# SV601275A.net
KiCad netlist of a schematic drawn in Altium Designer
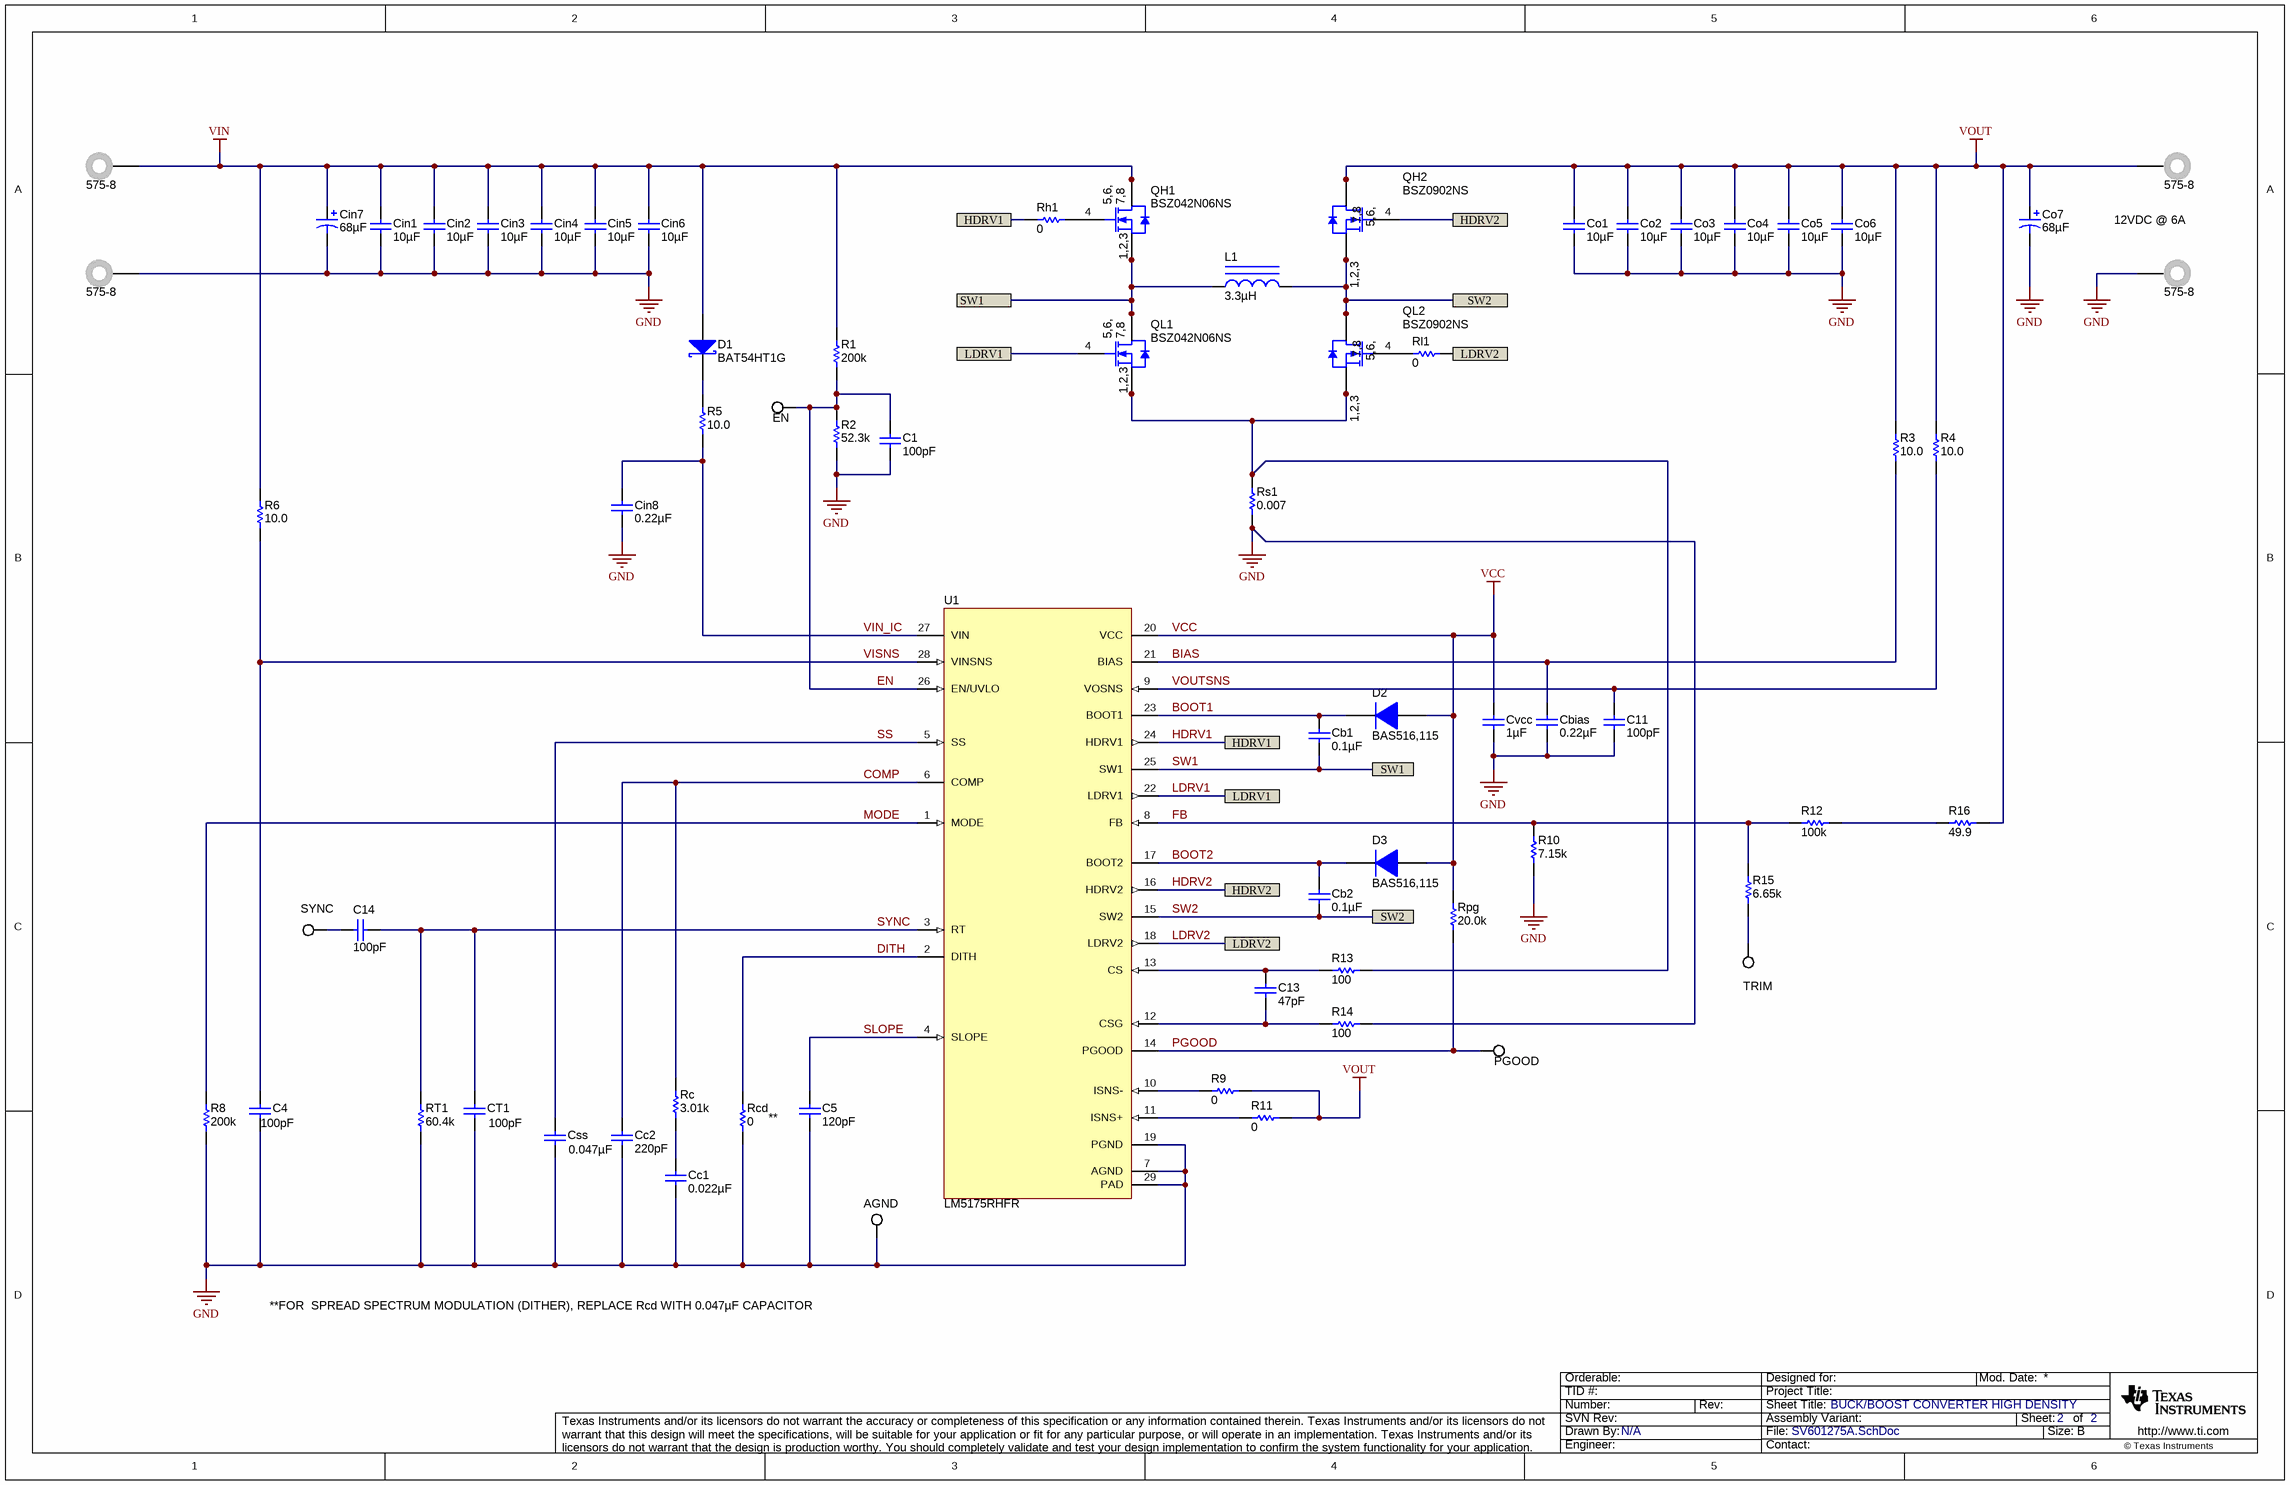
[diagram p0: SV601275A.SchDoc]

(export (version "E")
  (design (tool "Eeschema 10.0.6"))
  (components
    (comp (ref "AGND")
      (value "5015")
      (footprint "Testpoint_Keystone_Miniature")
      (description "Test Point, Miniature, SMT")
      (fields (field (name "MANUFACTURER") "Keystone") (field (name "PUBLISHER") "Texas Instruments"))
      (libsource (lib "Connectors_Keystone") (part "5015"))
    )
    (comp (ref "C1")
      (value "GRM1885C1H101JA01D")
      (footprint "0603L")
      (description "CAP, CERM, 100pF, 50V, +/-5%, C0G/NP0, 0603")
      (fields
        (field (name "VALUEDISPLAYED") "100pF")
        (field (name "MANUFACTURER") "MuRata")
        (field (name "PUBLISHER") "Texas Instruments")
      )
      (libsource (lib "Capacitor_Ceramic") (part "GRM1885C1H101JA01D"))
    )
    (comp (ref "C4")
      (value "GRM1885C1H101JA01D")
      (footprint "0603L")
      (description "CAP, CERM, 100pF, 50V, +/-5%, C0G/NP0, 0603")
      (fields
        (field (name "VALUEDISPLAYED") "100pF")
        (field (name "MANUFACTURER") "MuRata")
        (field (name "PUBLISHER") "Texas Instruments")
      )
      (libsource (lib "Capacitor_Ceramic") (part "GRM1885C1H101JA01D"))
    )
    (comp (ref "C5")
      (value "GRM1885C1H121JA01D")
      (footprint "0603L")
      (description "CAP, CERM, 120pF, 50V, +/-5%, C0G/NP0, 0603")
      (fields
        (field (name "VALUEDISPLAYED") "120pF")
        (field (name "MANUFACTURER") "MuRata")
        (field (name "PUBLISHER") "Texas Instruments")
      )
      (libsource (lib "Capacitor_Ceramic") (part "GRM1885C1H121JA01D"))
    )
    (comp (ref "C11")
      (value "GRM1885C1H101JA01D")
      (footprint "0603L")
      (description "CAP, CERM, 100pF, 50V, +/-5%, C0G/NP0, 0603")
      (fields
        (field (name "VALUEDISPLAYED") "100pF")
        (field (name "MANUFACTURER") "MuRata")
        (field (name "PUBLISHER") "Texas Instruments")
      )
      (libsource (lib "Capacitor_Ceramic") (part "GRM1885C1H101JA01D"))
    )
    (comp (ref "C13")
      (value "GRM1885C1H470JA01D")
      (footprint "0603L")
      (description "CAP, CERM, 47pF, 50V, +/-5%, C0G/NP0, 0603")
      (fields
        (field (name "VALUEDISPLAYED") "47pF")
        (field (name "MANUFACTURER") "MuRata")
        (field (name "PUBLISHER") "Texas Instruments")
      )
      (libsource (lib "Capacitor_Ceramic") (part "GRM1885C1H470JA01D"))
    )
    (comp (ref "C14")
      (value "CGA3E2NP01H101J080AA")
      (footprint "0603L")
      (description "CAP, CERM, 100pF, 50V, +/-5%, C0G/NP0, 0603")
      (fields
        (field (name "VALUEDISPLAYED") "100pF")
        (field (name "MANUFACTURER") "TDK")
        (field (name "PUBLISHER") "Texas Instruments")
      )
      (libsource (lib "Capacitor_Ceramic") (part "CGA3E2NP01H101J080AA"))
    )
    (comp (ref "Cb1")
      (value "GCM188R71H104KA57D")
      (footprint "0603L")
      (description "CAP, CERM, 0.1uF, 50V, +/-10%, X7R, 0603")
      (fields
        (field (name "VALUEDISPLAYED") "0.1µF")
        (field (name "MANUFACTURER") "MuRata")
        (field (name "PUBLISHER") "Texas Instruments")
      )
      (libsource (lib "Capacitor_Ceramic") (part "GCM188R71H104KA57D"))
    )
    (comp (ref "Cb2")
      (value "GCM188R71H104KA57D")
      (footprint "0603L")
      (description "CAP, CERM, 0.1uF, 50V, +/-10%, X7R, 0603")
      (fields
        (field (name "VALUEDISPLAYED") "0.1µF")
        (field (name "MANUFACTURER") "MuRata")
        (field (name "PUBLISHER") "Texas Instruments")
      )
      (libsource (lib "Capacitor_Ceramic") (part "GCM188R71H104KA57D"))
    )
    (comp (ref "Cbias")
      (value "C1608X7R1H224K080AB")
      (footprint "0603_HV")
      (description "CAP, CERM, 0.22uF, 50V, +/-10%, X7R, 0603")
      (fields
        (field (name "VALUEDISPLAYED") "0.22µF")
        (field (name "MANUFACTURER") "TDK")
        (field (name "PUBLISHER") "Texas Instruments")
      )
      (libsource (lib "Capacitor_Ceramic") (part "C1608X7R1H224K080AB"))
    )
    (comp (ref "Cc1")
      (value "GRM188R71H223KA01D")
      (footprint "0603L")
      (description "CAP, CERM, 0.022 µF, 50 V, +/- 10%, X7R, 0603")
      (fields
        (field (name "VALUEDISPLAYED") "0.022µF")
        (field (name "MANUFACTURER") "MuRata")
        (field (name "PUBLISHER") "Texas Instruments")
      )
      (libsource (lib "Capacitor_Ceramic") (part "GRM188R71H223KA01D"))
    )
    (comp (ref "Cc2")
      (value "GRM1885C1H221JA01D")
      (footprint "0603L")
      (description "CAP, CERM, 220 pF, 50 V, +/- 5%, C0G/NP0, 0603")
      (fields
        (field (name "VALUEDISPLAYED") "220pF")
        (field (name "MANUFACTURER") "MuRata")
        (field (name "PUBLISHER") "Texas Instruments")
      )
      (libsource (lib "Capacitor_Ceramic") (part "GRM1885C1H221JA01D"))
    )
    (comp (ref "Cin1")
      (value "GRM32ER71H106KA12L")
      (footprint "1210L")
      (description "CAP, CERM, 10uF, 50V, +/-10%, X7R, 1210")
      (fields
        (field (name "VALUEDISPLAYED") "10µF")
        (field (name "MANUFACTURER") "MuRata")
        (field (name "PUBLISHER") "Texas Instruments")
      )
      (libsource (lib "Capacitor_Ceramic") (part "GRM32ER71H106KA12L"))
    )
    (comp (ref "Cin2")
      (value "GRM32ER71H106KA12L")
      (footprint "1210L")
      (description "CAP, CERM, 10uF, 50V, +/-10%, X7R, 1210")
      (fields
        (field (name "VALUEDISPLAYED") "10µF")
        (field (name "MANUFACTURER") "MuRata")
        (field (name "PUBLISHER") "Texas Instruments")
      )
      (libsource (lib "Capacitor_Ceramic") (part "GRM32ER71H106KA12L"))
    )
    (comp (ref "Cin3")
      (value "GRM32ER71H106KA12L")
      (footprint "1210L")
      (description "CAP, CERM, 10uF, 50V, +/-10%, X7R, 1210")
      (fields
        (field (name "VALUEDISPLAYED") "10µF")
        (field (name "MANUFACTURER") "MuRata")
        (field (name "PUBLISHER") "Texas Instruments")
      )
      (libsource (lib "Capacitor_Ceramic") (part "GRM32ER71H106KA12L"))
    )
    (comp (ref "Cin4")
      (value "GRM32ER71H106KA12L")
      (footprint "1210L")
      (description "CAP, CERM, 10uF, 50V, +/-10%, X7R, 1210")
      (fields
        (field (name "VALUEDISPLAYED") "10µF")
        (field (name "MANUFACTURER") "MuRata")
        (field (name "PUBLISHER") "Texas Instruments")
      )
      (libsource (lib "Capacitor_Ceramic") (part "GRM32ER71H106KA12L"))
    )
    (comp (ref "Cin5")
      (value "GRM32ER71H106KA12L")
      (footprint "1210L")
      (description "CAP, CERM, 10uF, 50V, +/-10%, X7R, 1210")
      (fields
        (field (name "VALUEDISPLAYED") "10µF")
        (field (name "MANUFACTURER") "MuRata")
        (field (name "PUBLISHER") "Texas Instruments")
      )
      (libsource (lib "Capacitor_Ceramic") (part "GRM32ER71H106KA12L"))
    )
    (comp (ref "Cin6")
      (value "GRM32ER71H106KA12L")
      (footprint "1210L")
      (description "CAP, CERM, 10uF, 50V, +/-10%, X7R, 1210")
      (fields
        (field (name "VALUEDISPLAYED") "10µF")
        (field (name "MANUFACTURER") "MuRata")
        (field (name "PUBLISHER") "Texas Instruments")
      )
      (libsource (lib "Capacitor_Ceramic") (part "GRM32ER71H106KA12L"))
    )
    (comp (ref "Cin7")
      (value "EEHZC1H680P")
      (footprint "SM_RADIAL_8MM")
      (description "CAP, AL, 68 µF, 50 V, +/- 20%, 30 ohm, SMD")
      (fields
        (field (name "VALUEDISPLAYED") "68µF")
        (field (name "MANUFACTURER") "Panasonic")
        (field (name "PUBLISHER") "Texas Instruments")
      )
      (libsource (lib "Capacitor_Other") (part "EEHZC1H680P"))
    )
    (comp (ref "Cin8")
      (value "C1608X7R1H224K080AB")
      (footprint "0603L")
      (description "CAP, CERM, 0.22uF, 50V, +/-10%, X7R, 0603")
      (fields
        (field (name "VALUEDISPLAYED") "0.22µF")
        (field (name "MANUFACTURER") "TDK")
        (field (name "PUBLISHER") "Texas Instruments")
      )
      (libsource (lib "Capacitor_Ceramic") (part "C1608X7R1H224K080AB"))
    )
    (comp (ref "Co1")
      (value "GRM32ER71H106KA12L")
      (footprint "1210L")
      (description "CAP, CERM, 10 µF, 50 V, +/- 10%, X7R, 1210")
      (fields
        (field (name "VALUEDISPLAYED") "10µF")
        (field (name "MANUFACTURER") "MuRata")
        (field (name "PUBLISHER") "Texas Instruments")
      )
      (libsource (lib "Capacitor_Ceramic") (part "GRM32ER71H106KA12L"))
    )
    (comp (ref "Co2")
      (value "GRM32ER71H106KA12L")
      (footprint "1210L")
      (description "CAP, CERM, 10 µF, 50 V, +/- 10%, X7R, 1210")
      (fields
        (field (name "VALUEDISPLAYED") "10µF")
        (field (name "MANUFACTURER") "MuRata")
        (field (name "PUBLISHER") "Texas Instruments")
      )
      (libsource (lib "Capacitor_Ceramic") (part "GRM32ER71H106KA12L"))
    )
    (comp (ref "Co3")
      (value "GRM32ER71H106KA12L")
      (footprint "1210L")
      (description "CAP, CERM, 10 µF, 50 V, +/- 10%, X7R, 1210")
      (fields
        (field (name "VALUEDISPLAYED") "10µF")
        (field (name "MANUFACTURER") "MuRata")
        (field (name "PUBLISHER") "Texas Instruments")
      )
      (libsource (lib "Capacitor_Ceramic") (part "GRM32ER71H106KA12L"))
    )
    (comp (ref "Co4")
      (value "GRM32ER71H106KA12L")
      (footprint "1210L")
      (description "CAP, CERM, 10 µF, 50 V, +/- 10%, X7R, 1210")
      (fields
        (field (name "VALUEDISPLAYED") "10µF")
        (field (name "MANUFACTURER") "MuRata")
        (field (name "PUBLISHER") "Texas Instruments")
      )
      (libsource (lib "Capacitor_Ceramic") (part "GRM32ER71H106KA12L"))
    )
    (comp (ref "Co5")
      (value "GRM32ER71H106KA12L")
      (footprint "1210L")
      (description "CAP, CERM, 10 µF, 50 V, +/- 10%, X7R, 1210")
      (fields
        (field (name "VALUEDISPLAYED") "10µF")
        (field (name "MANUFACTURER") "MuRata")
        (field (name "PUBLISHER") "Texas Instruments")
      )
      (libsource (lib "Capacitor_Ceramic") (part "GRM32ER71H106KA12L"))
    )
    (comp (ref "Co6")
      (value "GRM32ER71H106KA12L")
      (footprint "1210L")
      (description "CAP, CERM, 10 µF, 50 V, +/- 10%, X7R, 1210")
      (fields
        (field (name "VALUEDISPLAYED") "10µF")
        (field (name "MANUFACTURER") "MuRata")
        (field (name "PUBLISHER") "Texas Instruments")
      )
      (libsource (lib "Capacitor_Ceramic") (part "GRM32ER71H106KA12L"))
    )
    (comp (ref "Co7")
      (value "EEHZC1H680P")
      (footprint "SM_RADIAL_8MM")
      (description "CAP, AL, 68 µF, 50 V, +/- 20%, 30 ohm, SMD")
      (fields
        (field (name "VALUEDISPLAYED") "68µF")
        (field (name "MANUFACTURER") "Panasonic")
        (field (name "PUBLISHER") "Texas Instruments")
      )
      (libsource (lib "Capacitor_Other") (part "EEHZC1H680P"))
    )
    (comp (ref "Css")
      (value "GRM188R71H473KA61D")
      (footprint "0603L")
      (description "CAP, CERM, 0.047 µF, 50 V, +/- 10%, X7R, 0603")
      (fields
        (field (name "VALUEDISPLAYED") "0.047µF")
        (field (name "MANUFACTURER") "MuRata")
        (field (name "PUBLISHER") "Texas Instruments")
      )
      (libsource (lib "Capacitor_Ceramic") (part "GRM188R71H473KA61D"))
    )
    (comp (ref "CT1")
      (value "DNP")
      (footprint "0603L")
      (description "CAP, CERM, 100pF, 50V, +/-5%, C0G/NP0, 0603")
      (fields
        (field (name "PARTNUMBER") "GRM1885C1H101JA01D")
        (field (name "VALUEDISPLAYED") "100pF")
        (field (name "MANUFACTURER") "MuRata")
        (field (name "PUBLISHER") "Texas Instruments")
      )
      (libsource (lib "Capacitor_Ceramic") (part "GRM1885C1H101JA01D"))
    )
    (comp (ref "Cvcc")
      (value "GRM188R71C105KA12D")
      (footprint "0603L")
      (description "CAP, CERM, 1uF, 16V, +/-10%, X7R, 0603")
      (fields
        (field (name "VALUEDISPLAYED") "1µF")
        (field (name "MANUFACTURER") "MuRata")
        (field (name "PUBLISHER") "Texas Instruments")
      )
      (libsource (lib "Capacitor_Ceramic") (part "GRM188R71C105KA12D"))
    )
    (comp (ref "D1")
      (value "BAT54HT1G")
      (footprint "sod-323")
      (description "Diode, Schottky, 30V, 0.2A, SOD-323")
      (fields (field (name "MANUFACTURER") "ON Semiconductor") (field (name "PUBLISHER") "Texas Instruments"))
      (libsource (lib "Diode") (part "BAT54HT1G"))
    )
    (comp (ref "D2")
      (value "BAS516,115")
      (footprint "SOD-523")
      (description "Diode, Switching, 100V, 0.25A, SOD-523")
      (fields
        (field (name "MANUFACTURER") "NXP Semiconductor")
        (field (name "PUBLISHER") "Texas Instruments")
      )
      (libsource (lib "Diode") (part "BAS516,115"))
    )
    (comp (ref "D3")
      (value "BAS516,115")
      (footprint "SOD-523")
      (description "Diode, Switching, 100V, 0.25A, SOD-523")
      (fields
        (field (name "MANUFACTURER") "NXP Semiconductor")
        (field (name "PUBLISHER") "Texas Instruments")
      )
      (libsource (lib "Diode") (part "BAS516,115"))
    )
    (comp (ref "EN")
      (value "5015")
      (footprint "Testpoint_Keystone_Miniature")
      (description "Test Point, Miniature, SMT")
      (fields (field (name "MANUFACTURER") "Keystone") (field (name "PUBLISHER") "Texas Instruments"))
      (libsource (lib "Connectors_Keystone") (part "5015"))
    )
    (comp (ref "J1")
      (value "575-8")
      (footprint "Keystone575-8")
      (description "Standard Banana Jack, Uninsulated, 8.9mm")
      (fields (field (name "MANUFACTURER") "Keystone") (field (name "PUBLISHER") "Texas Instruments"))
      (libsource (lib "Connectors_Keystone") (part "575-8"))
    )
    (comp (ref "J2")
      (value "575-8")
      (footprint "Keystone575-8")
      (description "Standard Banana Jack, Uninsulated, 8.9mm")
      (fields (field (name "MANUFACTURER") "Keystone") (field (name "PUBLISHER") "Texas Instruments"))
      (libsource (lib "Connectors_Keystone") (part "575-8"))
    )
    (comp (ref "J3")
      (value "575-8")
      (footprint "Keystone575-8")
      (description "Standard Banana Jack, Uninsulated, 8.9mm")
      (fields (field (name "MANUFACTURER") "Keystone") (field (name "PUBLISHER") "Texas Instruments"))
      (libsource (lib "Connectors_Keystone") (part "575-8"))
    )
    (comp (ref "J4")
      (value "575-8")
      (footprint "Keystone575-8")
      (description "Standard Banana Jack, Uninsulated, 8.9mm")
      (fields (field (name "MANUFACTURER") "Keystone") (field (name "PUBLISHER") "Texas Instruments"))
      (libsource (lib "Connectors_Keystone") (part "575-8"))
    )
    (comp (ref "L1")
      (value "IHLP5050FDER3R3M01")
      (footprint "IHLP-5050FD")
      (description "Inductor, Shielded Drum Core, Powdered Iron, 3.3 µH, 18 A, 0.0057 ohm, SMD")
      (fields
        (field (name "VALUEDISPLAYED") "3.3µH")
        (field (name "MANUFACTURER") "Vishay-Dale")
        (field (name "PUBLISHER") "Texas Instruments")
      )
      (libsource (lib "Inductor_Vishay") (part "IHLP5050FDER3R3M01"))
    )
    (comp (ref "PGOOD")
      (value "5015")
      (footprint "Testpoint_Keystone_Miniature")
      (description "Test Point, Miniature, SMT")
      (fields (field (name "MANUFACTURER") "Keystone") (field (name "PUBLISHER") "Texas Instruments"))
      (libsource (lib "Connectors_Keystone") (part "5015"))
    )
    (comp (ref "QH1")
      (value "BSZ042N06NS")
      (footprint "FETS:PG-TSDSON-8")
      (description "MOSFET N-CH 60V 19A 8TSDSON")
      (fields (field (name "MANUFACTURER") "Infineon Technologies") (field (name "SYMBOLCREATOR") "Use a-id"))
      (libsource (lib "FETs") (part "BSZ042N06NS"))
    )
    (comp (ref "QH2")
      (value "BSZ0902NS")
      (footprint "PG-TSDSON-8")
      (description "MOSFET, N-CH, 30V, 40A, PG-TSDSON-8")
      (fields
        (field (name "MANUFACTURER") "Infineon Technologies")
        (field (name "PUBLISHER") "Texas Instruments")
      )
      (libsource (lib "FETs") (part "BSZ0902NS"))
    )
    (comp (ref "QL1")
      (value "BSZ042N06NS")
      (footprint "FETS:PG-TSDSON-8")
      (description "MOSFET N-CH 60V 19A 8TSDSON")
      (fields (field (name "MANUFACTURER") "Infineon Technologies") (field (name "SYMBOLCREATOR") "Use a-id"))
      (libsource (lib "FETs") (part "BSZ042N06NS"))
    )
    (comp (ref "QL2")
      (value "BSZ0902NS")
      (footprint "PG-TSDSON-8")
      (description "MOSFET, N-CH, 30V, 40A, PG-TSDSON-8")
      (fields
        (field (name "MANUFACTURER") "Infineon Technologies")
        (field (name "PUBLISHER") "Texas Instruments")
      )
      (libsource (lib "FETs") (part "BSZ0902NS"))
    )
    (comp (ref "R1")
      (value "200k")
      (footprint "0603L")
      (description "RES, 200k ohm, 1%, 0.1W, 0603")
      (fields
        (field (name "PARTNUMBER") "RC0603FR-07200KL")
        (field (name "MANUFACTURER") "Yageo America")
        (field (name "PUBLISHER") "Texas Instruments")
      )
      (libsource (lib "Resistor_0603") (part "RC0603FR-07200KL"))
    )
    (comp (ref "R2")
      (value "RC0603FR-0752K3L")
      (footprint "0603L")
      (description "RES, 52.3 k, 1%, 0.1 W, 0603")
      (fields
        (field (name "MANUFACTURER") "Yageo America")
        (field (name "VALUEDISPLAYED") "52.3k")
        (field (name "PUBLISHER") "Texas Instruments")
      )
      (libsource (lib "Resistor_0603") (part "RC0603FR-0752K3L"))
    )
    (comp (ref "R3")
      (value "10.0")
      (footprint "0603_HV")
      (description "RES, 10.0 ohm, 1%, 0.1W, 0603")
      (fields
        (field (name "PARTNUMBER") "RC0603FR-0710RL")
        (field (name "MANUFACTURER") "Yageo America")
        (field (name "PUBLISHER") "Texas Instruments")
      )
      (libsource (lib "Resistor_0603") (part "RC0603FR-0710RL"))
    )
    (comp (ref "R4")
      (value "CRCW060310R0FKEA")
      (footprint "0603L")
      (description "RES, 10.0, 1%, 0.1 W, 0603")
      (fields
        (field (name "MANUFACTURER") "Vishay-Dale")
        (field (name "VALUEDISPLAYED") "10.0")
        (field (name "PUBLISHER") "Texas Instruments")
      )
      (libsource (lib "Resistor_0603") (part "CRCW060310R0FKEA"))
    )
    (comp (ref "R5")
      (value "10.0")
      (footprint "0603L")
      (description "RES, 10.0 ohm, 1%, 0.1W, 0603")
      (fields
        (field (name "PARTNUMBER") "RC0603FR-0710RL")
        (field (name "MANUFACTURER") "Yageo America")
        (field (name "PUBLISHER") "Texas Instruments")
      )
      (libsource (lib "Resistor_0603") (part "RC0603FR-0710RL"))
    )
    (comp (ref "R6")
      (value "10.0")
      (footprint "0603L")
      (description "RES, 10.0 ohm, 1%, 0.1W, 0603")
      (fields
        (field (name "PARTNUMBER") "RC0603FR-0710RL")
        (field (name "MANUFACTURER") "Yageo America")
        (field (name "PUBLISHER") "Texas Instruments")
      )
      (libsource (lib "Resistor_0603") (part "RC0603FR-0710RL"))
    )
    (comp (ref "R8")
      (value "CRCW0603200KFKEA")
      (footprint "0603L")
      (description "RES, 200 k, 1%, 0.1 W, 0603")
      (fields
        (field (name "MANUFACTURER") "Vishay-Dale")
        (field (name "VALUEDISPLAYED") "200k")
        (field (name "PUBLISHER") "Texas Instruments")
      )
      (libsource (lib "Resistor_0603") (part "CRCW0603200KFKEA"))
    )
    (comp (ref "R9")
      (value "RC0603JR-070RL")
      (footprint "0603L")
      (description "RES, 0, 5%, 0.1 W, 0603")
      (fields
        (field (name "MANUFACTURER") "Yageo America")
        (field (name "VALUEDISPLAYED") "0")
        (field (name "PUBLISHER") "Texas Instruments")
      )
      (libsource (lib "Resistor_0603") (part "RC0603JR-070RL"))
    )
    (comp (ref "R10")
      (value "7.15k")
      (footprint "0603L")
      (description "RES, 7.15k ohm, 1%, 0.1W, 0603")
      (fields
        (field (name "PARTNUMBER") "RC0603FR-077K15L")
        (field (name "MANUFACTURER") "Yageo America")
        (field (name "PUBLISHER") "Texas Instruments")
      )
      (libsource (lib "Resistor_0603") (part "RC0603FR-077K15L"))
    )
    (comp (ref "R11")
      (value "RC0603JR-070RL")
      (footprint "0603L")
      (description "RES, 0, 5%, 0.1 W, 0603")
      (fields
        (field (name "MANUFACTURER") "Yageo America")
        (field (name "VALUEDISPLAYED") "0")
        (field (name "PUBLISHER") "Texas Instruments")
      )
      (libsource (lib "Resistor_0603") (part "RC0603JR-070RL"))
    )
    (comp (ref "R12")
      (value "100k")
      (footprint "0603L")
      (description "RES, 100k ohm, 1%, 0.1W, 0603")
      (fields
        (field (name "PARTNUMBER") "RC0603FR-07100KL")
        (field (name "MANUFACTURER") "Yageo America")
        (field (name "PUBLISHER") "Texas Instruments")
      )
      (libsource (lib "Resistor_0603") (part "RC0603FR-07100KL"))
    )
    (comp (ref "R13")
      (value "100")
      (footprint "0603L")
      (description "RES, 100 ohm, 1%, 0.1W, 0603")
      (fields
        (field (name "PARTNUMBER") "RC0603FR-07100RL")
        (field (name "MANUFACTURER") "Yageo America")
        (field (name "PUBLISHER") "Texas Instruments")
      )
      (libsource (lib "Resistor_0603") (part "RC0603FR-07100RL"))
    )
    (comp (ref "R14")
      (value "100")
      (footprint "0603L")
      (description "RES, 100 ohm, 1%, 0.1W, 0603")
      (fields
        (field (name "PARTNUMBER") "RC0603FR-07100RL")
        (field (name "MANUFACTURER") "Yageo America")
        (field (name "PUBLISHER") "Texas Instruments")
      )
      (libsource (lib "Resistor_0603") (part "RC0603FR-07100RL"))
    )
    (comp (ref "R15")
      (value "RC0603FR-076K65L")
      (footprint "0603L")
      (description "RES, 6.65 k, 1%, 0.1 W, 0603")
      (fields
        (field (name "MANUFACTURER") "Yageo America")
        (field (name "VALUEDISPLAYED") "6.65k")
        (field (name "PUBLISHER") "Texas Instruments")
      )
      (libsource (lib "Resistor_0603") (part "RC0603FR-076K65L"))
    )
    (comp (ref "R16")
      (value "CRCW060349R9FKEA")
      (footprint "0603")
      (description "RES, 49.9, 1%, 0.1 W, 0603")
      (fields
        (field (name "MANUFACTURER") "Vishay-Dale")
        (field (name "VALUEDISPLAYED") "49.9")
        (field (name "PUBLISHER") "Texas Instruments")
      )
      (libsource (lib "Resistor_0603") (part "CRCW060349R9FKEA"))
    )
    (comp (ref "Rc")
      (value "3.01k")
      (footprint "0603L")
      (description "RES, 3.01k ohm, 1%, 0.1W, 0603")
      (fields
        (field (name "PARTNUMBER") "RC0603FR-073K01L")
        (field (name "MANUFACTURER") "Yageo America")
        (field (name "PUBLISHER") "Texas Instruments")
      )
      (libsource (lib "Resistor_0603") (part "RC0603FR-073K01L"))
    )
    (comp (ref "Rcd")
      (value "RC0603JR-070RL")
      (footprint "0603L")
      (description "RES, 0, 5%, 0.1 W, 0603")
      (fields
        (field (name "MANUFACTURER") "Yageo America")
        (field (name "VALUEDISPLAYED") "0")
        (field (name "PUBLISHER") "Texas Instruments")
      )
      (libsource (lib "Resistor_0603") (part "RC0603JR-070RL"))
    )
    (comp (ref "Rh1")
      (value "0")
      (footprint "0603L")
      (description "RES, 0 ohm, 5%, 0.1W, 0603")
      (fields
        (field (name "PARTNUMBER") "CRCW06030000Z0EA")
        (field (name "MANUFACTURER") "Vishay-Dale")
        (field (name "PUBLISHER") "Texas Instruments")
      )
      (libsource (lib "Resistor_0603") (part "CRCW06030000Z0EA"))
    )
    (comp (ref "Rl1")
      (value "0")
      (footprint "0603L")
      (description "RES, 0 ohm, 5%, 0.1W, 0603")
      (fields
        (field (name "PARTNUMBER") "CRCW06030000Z0EA")
        (field (name "MANUFACTURER") "Vishay-Dale")
        (field (name "PUBLISHER") "Texas Instruments")
      )
      (libsource (lib "Resistor_0603") (part "CRCW06030000Z0EA"))
    )
    (comp (ref "Rpg")
      (value "RC0603FR-0720KL")
      (footprint "0603L")
      (description "RES, 20.0 k, 1%, 0.1 W, 0603")
      (fields
        (field (name "MANUFACTURER") "Yageo America")
        (field (name "VALUEDISPLAYED") "20.0k")
        (field (name "PUBLISHER") "Texas Instruments")
      )
      (libsource (lib "Resistor_0603") (part "RC0603FR-0720KL"))
    )
    (comp (ref "Rs1")
      (value "0.007")
      (footprint "Resistor_OtherSMT:2512_WIDE")
      (description "RES 0.007 OHM 3W 1% 2512 WIDE")
      (fields
        (field (name "PARTNUMBER") "KRL6432E-M-R007-F-T1")
        (field (name "MANUFACTURER") "Susumu")
        (field (name "SYMBOLCREATOR") "Use a-id")
      )
      (libsource (lib "Resistor_OtherSMT") (part "KRL6432E-M-R007-F-T1"))
    )
    (comp (ref "RT1")
      (value "RC0603FR-0760K4L")
      (footprint "0603L")
      (description "RES, 60.4 k, 1%, 0.1 W, 0603")
      (fields
        (field (name "MANUFACTURER") "Yageo America")
        (field (name "VALUEDISPLAYED") "60.4k")
        (field (name "PUBLISHER") "Texas Instruments")
      )
      (libsource (lib "Resistor_0603") (part "RC0603FR-0760K4L"))
    )
    (comp (ref "SYNC")
      (value "5015")
      (footprint "Testpoint_Keystone_Miniature")
      (description "Test Point, Miniature, SMT")
      (fields (field (name "MANUFACTURER") "Keystone") (field (name "PUBLISHER") "Texas Instruments"))
      (libsource (lib "Connectors_Keystone") (part "5015"))
    )
    (comp (ref "TRIM")
      (value "5015")
      (footprint "Testpoint_Keystone_Miniature")
      (description "Test Point, Miniature, SMT")
      (fields (field (name "MANUFACTURER") "Keystone") (field (name "PUBLISHER") "Texas Instruments"))
      (libsource (lib "Connectors_Keystone") (part "5015"))
    )
    (comp (ref "U1")
      (value "LM5175RHFR")
      (footprint "RHF0028A")
      (description "42-V Wide VIN Synchronous 4-Switch Buck-Boost Controller, RHF0028A")
      (fields
        (field (name "ALTERNATE PARTNUMBER") "LM5175RHFT")
        (field (name "MANUFACTURER") "Texas Instruments")
        (field (name "SYMBOLCREATOR") "Altium")
        (field (name "PUBLISHER") "Texas Instruments")
      )
      (libsource (lib "TI_Pre_RTM") (part "LM5175RHFR"))
    )
  )
  (nets
    (net (code "1") (name "/BIAS") (class "Default")
      (node (ref "Cbias") (pin "1") (pinfunction "1_1") (pintype "passive"))
      (node (ref "R3") (pin "1") (pinfunction "1_1") (pintype "passive"))
      (node (ref "U1") (pin "21") (pinfunction "BIAS_21") (pintype "power_in"))
    )
    (net (code "2") (name "/BOOT1") (class "Default")
      (node (ref "Cb1") (pin "1") (pinfunction "1_1") (pintype "passive"))
      (node (ref "D2") (pin "1") (pinfunction "K_1") (pintype "passive"))
      (node (ref "U1") (pin "23") (pinfunction "BOOT1_23") (pintype "power_in"))
    )
    (net (code "3") (name "/BOOT2") (class "Default")
      (node (ref "Cb2") (pin "2") (pinfunction "2_2") (pintype "passive"))
      (node (ref "D3") (pin "1") (pinfunction "K_1") (pintype "passive"))
      (node (ref "U1") (pin "17") (pinfunction "BOOT2_17") (pintype "power_in"))
    )
    (net (code "4") (name "/COMP") (class "Default")
      (node (ref "Cc2") (pin "2") (pinfunction "2_2") (pintype "passive"))
      (node (ref "Rc") (pin "2") (pinfunction "2_2") (pintype "passive"))
      (node (ref "U1") (pin "6") (pinfunction "COMP_6") (pintype "passive"))
    )
    (net (code "5") (name "/DITH") (class "Default")
      (node (ref "Rcd") (pin "2") (pinfunction "2_2") (pintype "passive"))
      (node (ref "U1") (pin "2") (pinfunction "DITH_2") (pintype "passive"))
    )
    (net (code "6") (name "/EN") (class "Default")
      (node (ref "C1") (pin "2") (pinfunction "2_2") (pintype "passive"))
      (node (ref "EN") (pin "1") (pintype "passive"))
      (node (ref "R1") (pin "1") (pinfunction "1_1") (pintype "passive"))
      (node (ref "R2") (pin "2") (pinfunction "2_2") (pintype "passive"))
      (node (ref "U1") (pin "26") (pinfunction "EN/UVLO_26") (pintype "input"))
    )
    (net (code "7") (name "/FB") (class "Default")
      (node (ref "R10") (pin "1") (pinfunction "1_1") (pintype "passive"))
      (node (ref "R12") (pin "2") (pinfunction "2_2") (pintype "passive"))
      (node (ref "R15") (pin "2") (pinfunction "2_2") (pintype "passive"))
      (node (ref "U1") (pin "8") (pinfunction "FB_8") (pintype "input"))
    )
    (net (code "8") (name "/HDRV1") (class "Default")
      (node (ref "Rh1") (pin "1") (pinfunction "1_1") (pintype "passive"))
      (node (ref "U1") (pin "24") (pinfunction "HDRV1_24") (pintype "output"))
    )
    (net (code "9") (name "/HDRV2") (class "Default")
      (node (ref "QH2") (pin "4") (pinfunction "G_4") (pintype "passive"))
      (node (ref "U1") (pin "16") (pinfunction "HDRV2_16") (pintype "output"))
    )
    (net (code "10") (name "/LDRV1") (class "Default")
      (node (ref "QL1") (pin "4") (pinfunction "G_4") (pintype "passive"))
      (node (ref "U1") (pin "22") (pinfunction "LDRV1_22") (pintype "output"))
    )
    (net (code "11") (name "/LDRV2") (class "Default")
      (node (ref "Rl1") (pin "2") (pinfunction "2_2") (pintype "passive"))
      (node (ref "U1") (pin "18") (pinfunction "LDRV2_18") (pintype "output"))
    )
    (net (code "12") (name "/MODE") (class "Default")
      (node (ref "R8") (pin "2") (pinfunction "2_2") (pintype "passive"))
      (node (ref "U1") (pin "1") (pinfunction "MODE_1") (pintype "input"))
    )
    (net (code "13") (name "/PGOOD") (class "Default")
      (node (ref "PGOOD") (pin "1") (pintype "passive"))
      (node (ref "Rpg") (pin "2") (pinfunction "2_2") (pintype "passive"))
      (node (ref "U1") (pin "14") (pinfunction "PGOOD_14") (pintype "open_collector"))
    )
    (net (code "14") (name "/SLOPE") (class "Default")
      (node (ref "C5") (pin "1") (pinfunction "1_1") (pintype "passive"))
      (node (ref "U1") (pin "4") (pinfunction "SLOPE_4") (pintype "input"))
    )
    (net (code "15") (name "/SS") (class "Default")
      (node (ref "Css") (pin "1") (pinfunction "1_1") (pintype "passive"))
      (node (ref "U1") (pin "5") (pinfunction "SS_5") (pintype "input"))
    )
    (net (code "16") (name "/SW1") (class "Default")
      (node (ref "Cb1") (pin "2") (pinfunction "2_2") (pintype "passive"))
      (node (ref "L1") (pin "1") (pinfunction "1_1") (pintype "passive"))
      (node (ref "QH1") (pin "1") (pinfunction "S_1") (pintype "passive"))
      (node (ref "QH1") (pin "2") (pinfunction "S_2") (pintype "passive"))
      (node (ref "QH1") (pin "3") (pinfunction "S_3") (pintype "passive"))
      (node (ref "QL1") (pin "5") (pinfunction "D_5") (pintype "passive"))
      (node (ref "QL1") (pin "6") (pinfunction "D_6") (pintype "passive"))
      (node (ref "QL1") (pin "7") (pinfunction "D_7") (pintype "passive"))
      (node (ref "QL1") (pin "8") (pinfunction "D_8") (pintype "passive"))
      (node (ref "QL1") (pin "9") (pinfunction "D_9") (pintype "passive"))
      (node (ref "U1") (pin "25") (pinfunction "SW1_25") (pintype "power_in"))
    )
    (net (code "17") (name "/SW2") (class "Default")
      (node (ref "Cb2") (pin "1") (pinfunction "1_1") (pintype "passive"))
      (node (ref "L1") (pin "2") (pinfunction "2_2") (pintype "passive"))
      (node (ref "QH2") (pin "1") (pinfunction "S_1") (pintype "passive"))
      (node (ref "QH2") (pin "2") (pinfunction "S_2") (pintype "passive"))
      (node (ref "QH2") (pin "3") (pinfunction "S_3") (pintype "passive"))
      (node (ref "QL2") (pin "5") (pinfunction "D_5") (pintype "passive"))
      (node (ref "QL2") (pin "6") (pinfunction "D_6") (pintype "passive"))
      (node (ref "QL2") (pin "7") (pinfunction "D_7") (pintype "passive"))
      (node (ref "QL2") (pin "8") (pinfunction "D_8") (pintype "passive"))
      (node (ref "QL2") (pin "9") (pinfunction "D_9") (pintype "passive"))
      (node (ref "U1") (pin "15") (pinfunction "SW2_15") (pintype "power_in"))
    )
    (net (code "18") (name "/SYNC") (class "Default")
      (node (ref "C14") (pin "1") (pinfunction "1_1") (pintype "passive"))
      (node (ref "CT1") (pin "2") (pinfunction "2_2") (pintype "passive"))
      (node (ref "RT1") (pin "2") (pinfunction "2_2") (pintype "passive"))
      (node (ref "U1") (pin "3") (pinfunction "RT_3") (pintype "input"))
    )
    (net (code "19") (name "/VIN_IC") (class "Default")
      (node (ref "Cin8") (pin "1") (pinfunction "1_1") (pintype "passive"))
      (node (ref "R5") (pin "1") (pinfunction "1_1") (pintype "passive"))
      (node (ref "U1") (pin "27") (pinfunction "VIN_27") (pintype "power_in"))
    )
    (net (code "20") (name "/VISNS") (class "Default")
      (node (ref "C4") (pin "2") (pinfunction "2_2") (pintype "passive"))
      (node (ref "R6") (pin "2") (pinfunction "2_2") (pintype "passive"))
      (node (ref "U1") (pin "28") (pinfunction "VINSNS_28") (pintype "input"))
    )
    (net (code "21") (name "/VOUTSNS") (class "Default")
      (node (ref "C11") (pin "1") (pinfunction "1_1") (pintype "passive"))
      (node (ref "R4") (pin "1") (pinfunction "1_1") (pintype "passive"))
      (node (ref "U1") (pin "9") (pinfunction "VOSNS_9") (pintype "input"))
    )
    (net (code "22") (name "GND") (class "Default")
      (node (ref "AGND") (pin "1") (pintype "passive"))
      (node (ref "C1") (pin "1") (pinfunction "1_1") (pintype "passive"))
      (node (ref "C11") (pin "2") (pinfunction "2_2") (pintype "passive"))
      (node (ref "C4") (pin "1") (pinfunction "1_1") (pintype "passive"))
      (node (ref "C5") (pin "2") (pinfunction "2_2") (pintype "passive"))
      (node (ref "CT1") (pin "1") (pinfunction "1_1") (pintype "passive"))
      (node (ref "Cbias") (pin "2") (pinfunction "2_2") (pintype "passive"))
      (node (ref "Cc1") (pin "2") (pinfunction "2_2") (pintype "passive"))
      (node (ref "Cc2") (pin "1") (pinfunction "1_1") (pintype "passive"))
      (node (ref "Cin1") (pin "2") (pinfunction "2_2") (pintype "passive"))
      (node (ref "Cin2") (pin "2") (pinfunction "2_2") (pintype "passive"))
      (node (ref "Cin3") (pin "2") (pinfunction "2_2") (pintype "passive"))
      (node (ref "Cin4") (pin "2") (pinfunction "2_2") (pintype "passive"))
      (node (ref "Cin5") (pin "2") (pinfunction "2_2") (pintype "passive"))
      (node (ref "Cin6") (pin "2") (pinfunction "2_2") (pintype "passive"))
      (node (ref "Cin7") (pin "2") (pinfunction "-_2") (pintype "passive"))
      (node (ref "Cin8") (pin "2") (pinfunction "2_2") (pintype "passive"))
      (node (ref "Co1") (pin "2") (pinfunction "2_2") (pintype "passive"))
      (node (ref "Co2") (pin "2") (pinfunction "2_2") (pintype "passive"))
      (node (ref "Co3") (pin "2") (pinfunction "2_2") (pintype "passive"))
      (node (ref "Co4") (pin "2") (pinfunction "2_2") (pintype "passive"))
      (node (ref "Co5") (pin "2") (pinfunction "2_2") (pintype "passive"))
      (node (ref "Co6") (pin "2") (pinfunction "2_2") (pintype "passive"))
      (node (ref "Co7") (pin "2") (pinfunction "-_2") (pintype "passive"))
      (node (ref "Css") (pin "2") (pinfunction "2_2") (pintype "passive"))
      (node (ref "Cvcc") (pin "2") (pinfunction "2_2") (pintype "passive"))
      (node (ref "J3") (pin "1") (pinfunction "1_1") (pintype "passive"))
      (node (ref "J4") (pin "1") (pinfunction "1_1") (pintype "passive"))
      (node (ref "R10") (pin "2") (pinfunction "2_2") (pintype "passive"))
      (node (ref "R14") (pin "2") (pinfunction "2_2") (pintype "passive"))
      (node (ref "R2") (pin "1") (pinfunction "1_1") (pintype "passive"))
      (node (ref "R8") (pin "1") (pinfunction "1_1") (pintype "passive"))
      (node (ref "RT1") (pin "1") (pinfunction "1_1") (pintype "passive"))
      (node (ref "Rcd") (pin "1") (pinfunction "1_1") (pintype "passive"))
      (node (ref "Rs1") (pin "1") (pinfunction "1_1") (pintype "passive"))
      (node (ref "U1") (pin "19") (pinfunction "PGND_19") (pintype "power_in"))
      (node (ref "U1") (pin "29") (pinfunction "PAD_29") (pintype "power_in"))
      (node (ref "U1") (pin "7") (pinfunction "AGND_7") (pintype "power_in"))
    )
    (net (code "23") (name "Net-(C14-Pad2)") (class "Default")
      (node (ref "C14") (pin "2") (pinfunction "2_2") (pintype "passive"))
      (node (ref "SYNC") (pin "1") (pintype "passive"))
    )
    (net (code "24") (name "Net-(Cc1-Pad1)") (class "Default")
      (node (ref "Cc1") (pin "1") (pinfunction "1_1") (pintype "passive"))
      (node (ref "Rc") (pin "1") (pinfunction "1_1") (pintype "passive"))
    )
    (net (code "25") (name "Net-(D1-K)") (class "Default")
      (node (ref "D1") (pin "1") (pinfunction "K_1") (pintype "passive"))
      (node (ref "R5") (pin "2") (pinfunction "2_2") (pintype "passive"))
    )
    (net (code "26") (name "Net-(QH1-G)") (class "Default")
      (node (ref "QH1") (pin "4") (pinfunction "G_4") (pintype "passive"))
      (node (ref "Rh1") (pin "2") (pinfunction "2_2") (pintype "passive"))
    )
    (net (code "27") (name "Net-(QL1-S-Pad1)") (class "Default")
      (node (ref "QL1") (pin "1") (pinfunction "S_1") (pintype "passive"))
      (node (ref "QL1") (pin "2") (pinfunction "S_2") (pintype "passive"))
      (node (ref "QL1") (pin "3") (pinfunction "S_3") (pintype "passive"))
      (node (ref "QL2") (pin "1") (pinfunction "S_1") (pintype "passive"))
      (node (ref "QL2") (pin "2") (pinfunction "S_2") (pintype "passive"))
      (node (ref "QL2") (pin "3") (pinfunction "S_3") (pintype "passive"))
      (node (ref "R13") (pin "2") (pinfunction "2_2") (pintype "passive"))
      (node (ref "Rs1") (pin "2") (pinfunction "2_2") (pintype "passive"))
    )
    (net (code "28") (name "Net-(QL2-G)") (class "Default")
      (node (ref "QL2") (pin "4") (pinfunction "G_4") (pintype "passive"))
      (node (ref "Rl1") (pin "1") (pinfunction "1_1") (pintype "passive"))
    )
    (net (code "29") (name "Net-(R12-Pad1)") (class "Default")
      (node (ref "R12") (pin "1") (pinfunction "1_1") (pintype "passive"))
      (node (ref "R16") (pin "2") (pinfunction "2_2") (pintype "passive"))
    )
    (net (code "30") (name "Net-(R15-Pad1)") (class "Default")
      (node (ref "R15") (pin "1") (pinfunction "1_1") (pintype "passive"))
      (node (ref "TRIM") (pin "1") (pintype "passive"))
    )
    (net (code "31") (name "Net-(U1-CS)") (class "Default")
      (node (ref "C13") (pin "2") (pinfunction "2_2") (pintype "passive"))
      (node (ref "R13") (pin "1") (pinfunction "1_1") (pintype "passive"))
      (node (ref "U1") (pin "13") (pinfunction "CS_13") (pintype "input"))
    )
    (net (code "32") (name "Net-(U1-CSG)") (class "Default")
      (node (ref "C13") (pin "1") (pinfunction "1_1") (pintype "passive"))
      (node (ref "R14") (pin "1") (pinfunction "1_1") (pintype "passive"))
      (node (ref "U1") (pin "12") (pinfunction "CSG_12") (pintype "input"))
    )
    (net (code "33") (name "Net-(U1-ISNS+)") (class "Default")
      (node (ref "R11") (pin "2") (pinfunction "2_2") (pintype "passive"))
      (node (ref "U1") (pin "11") (pinfunction "ISNS+_11") (pintype "input"))
    )
    (net (code "34") (name "Net-(U1-ISNS-)") (class "Default")
      (node (ref "R9") (pin "2") (pinfunction "2_2") (pintype "passive"))
      (node (ref "U1") (pin "10") (pinfunction "ISNS-_10") (pintype "input"))
    )
    (net (code "35") (name "VCC") (class "Default")
      (node (ref "Cvcc") (pin "1") (pinfunction "1_1") (pintype "passive"))
      (node (ref "D2") (pin "2") (pinfunction "A_2") (pintype "passive"))
      (node (ref "D3") (pin "2") (pinfunction "A_2") (pintype "passive"))
      (node (ref "Rpg") (pin "1") (pinfunction "1_1") (pintype "passive"))
      (node (ref "U1") (pin "20") (pinfunction "VCC_20") (pintype "power_in"))
    )
    (net (code "36") (name "VIN") (class "Default")
      (node (ref "Cin1") (pin "1") (pinfunction "1_1") (pintype "passive"))
      (node (ref "Cin2") (pin "1") (pinfunction "1_1") (pintype "passive"))
      (node (ref "Cin3") (pin "1") (pinfunction "1_1") (pintype "passive"))
      (node (ref "Cin4") (pin "1") (pinfunction "1_1") (pintype "passive"))
      (node (ref "Cin5") (pin "1") (pinfunction "1_1") (pintype "passive"))
      (node (ref "Cin6") (pin "1") (pinfunction "1_1") (pintype "passive"))
      (node (ref "Cin7") (pin "1") (pinfunction "+_1") (pintype "passive"))
      (node (ref "D1") (pin "2") (pinfunction "A_2") (pintype "passive"))
      (node (ref "J1") (pin "1") (pinfunction "1_1") (pintype "passive"))
      (node (ref "QH1") (pin "5") (pinfunction "D_5") (pintype "passive"))
      (node (ref "QH1") (pin "6") (pinfunction "D_6") (pintype "passive"))
      (node (ref "QH1") (pin "7") (pinfunction "D_7") (pintype "passive"))
      (node (ref "QH1") (pin "8") (pinfunction "D_8") (pintype "passive"))
      (node (ref "QH1") (pin "9") (pinfunction "D_9") (pintype "passive"))
      (node (ref "R1") (pin "2") (pinfunction "2_2") (pintype "passive"))
      (node (ref "R6") (pin "1") (pinfunction "1_1") (pintype "passive"))
    )
    (net (code "37") (name "VOUT") (class "Default")
      (node (ref "Co1") (pin "1") (pinfunction "1_1") (pintype "passive"))
      (node (ref "Co2") (pin "1") (pinfunction "1_1") (pintype "passive"))
      (node (ref "Co3") (pin "1") (pinfunction "1_1") (pintype "passive"))
      (node (ref "Co4") (pin "1") (pinfunction "1_1") (pintype "passive"))
      (node (ref "Co5") (pin "1") (pinfunction "1_1") (pintype "passive"))
      (node (ref "Co6") (pin "1") (pinfunction "1_1") (pintype "passive"))
      (node (ref "Co7") (pin "1") (pinfunction "+_1") (pintype "passive"))
      (node (ref "J2") (pin "1") (pinfunction "1_1") (pintype "passive"))
      (node (ref "QH2") (pin "5") (pinfunction "D_5") (pintype "passive"))
      (node (ref "QH2") (pin "6") (pinfunction "D_6") (pintype "passive"))
      (node (ref "QH2") (pin "7") (pinfunction "D_7") (pintype "passive"))
      (node (ref "QH2") (pin "8") (pinfunction "D_8") (pintype "passive"))
      (node (ref "QH2") (pin "9") (pinfunction "D_9") (pintype "passive"))
      (node (ref "R11") (pin "1") (pinfunction "1_1") (pintype "passive"))
      (node (ref "R16") (pin "1") (pinfunction "1_1") (pintype "passive"))
      (node (ref "R3") (pin "2") (pinfunction "2_2") (pintype "passive"))
      (node (ref "R4") (pin "2") (pinfunction "2_2") (pintype "passive"))
      (node (ref "R9") (pin "1") (pinfunction "1_1") (pintype "passive"))
    )
  )
)
